# HUD.net
KiCad netlist of a schematic drawn in EAGLE
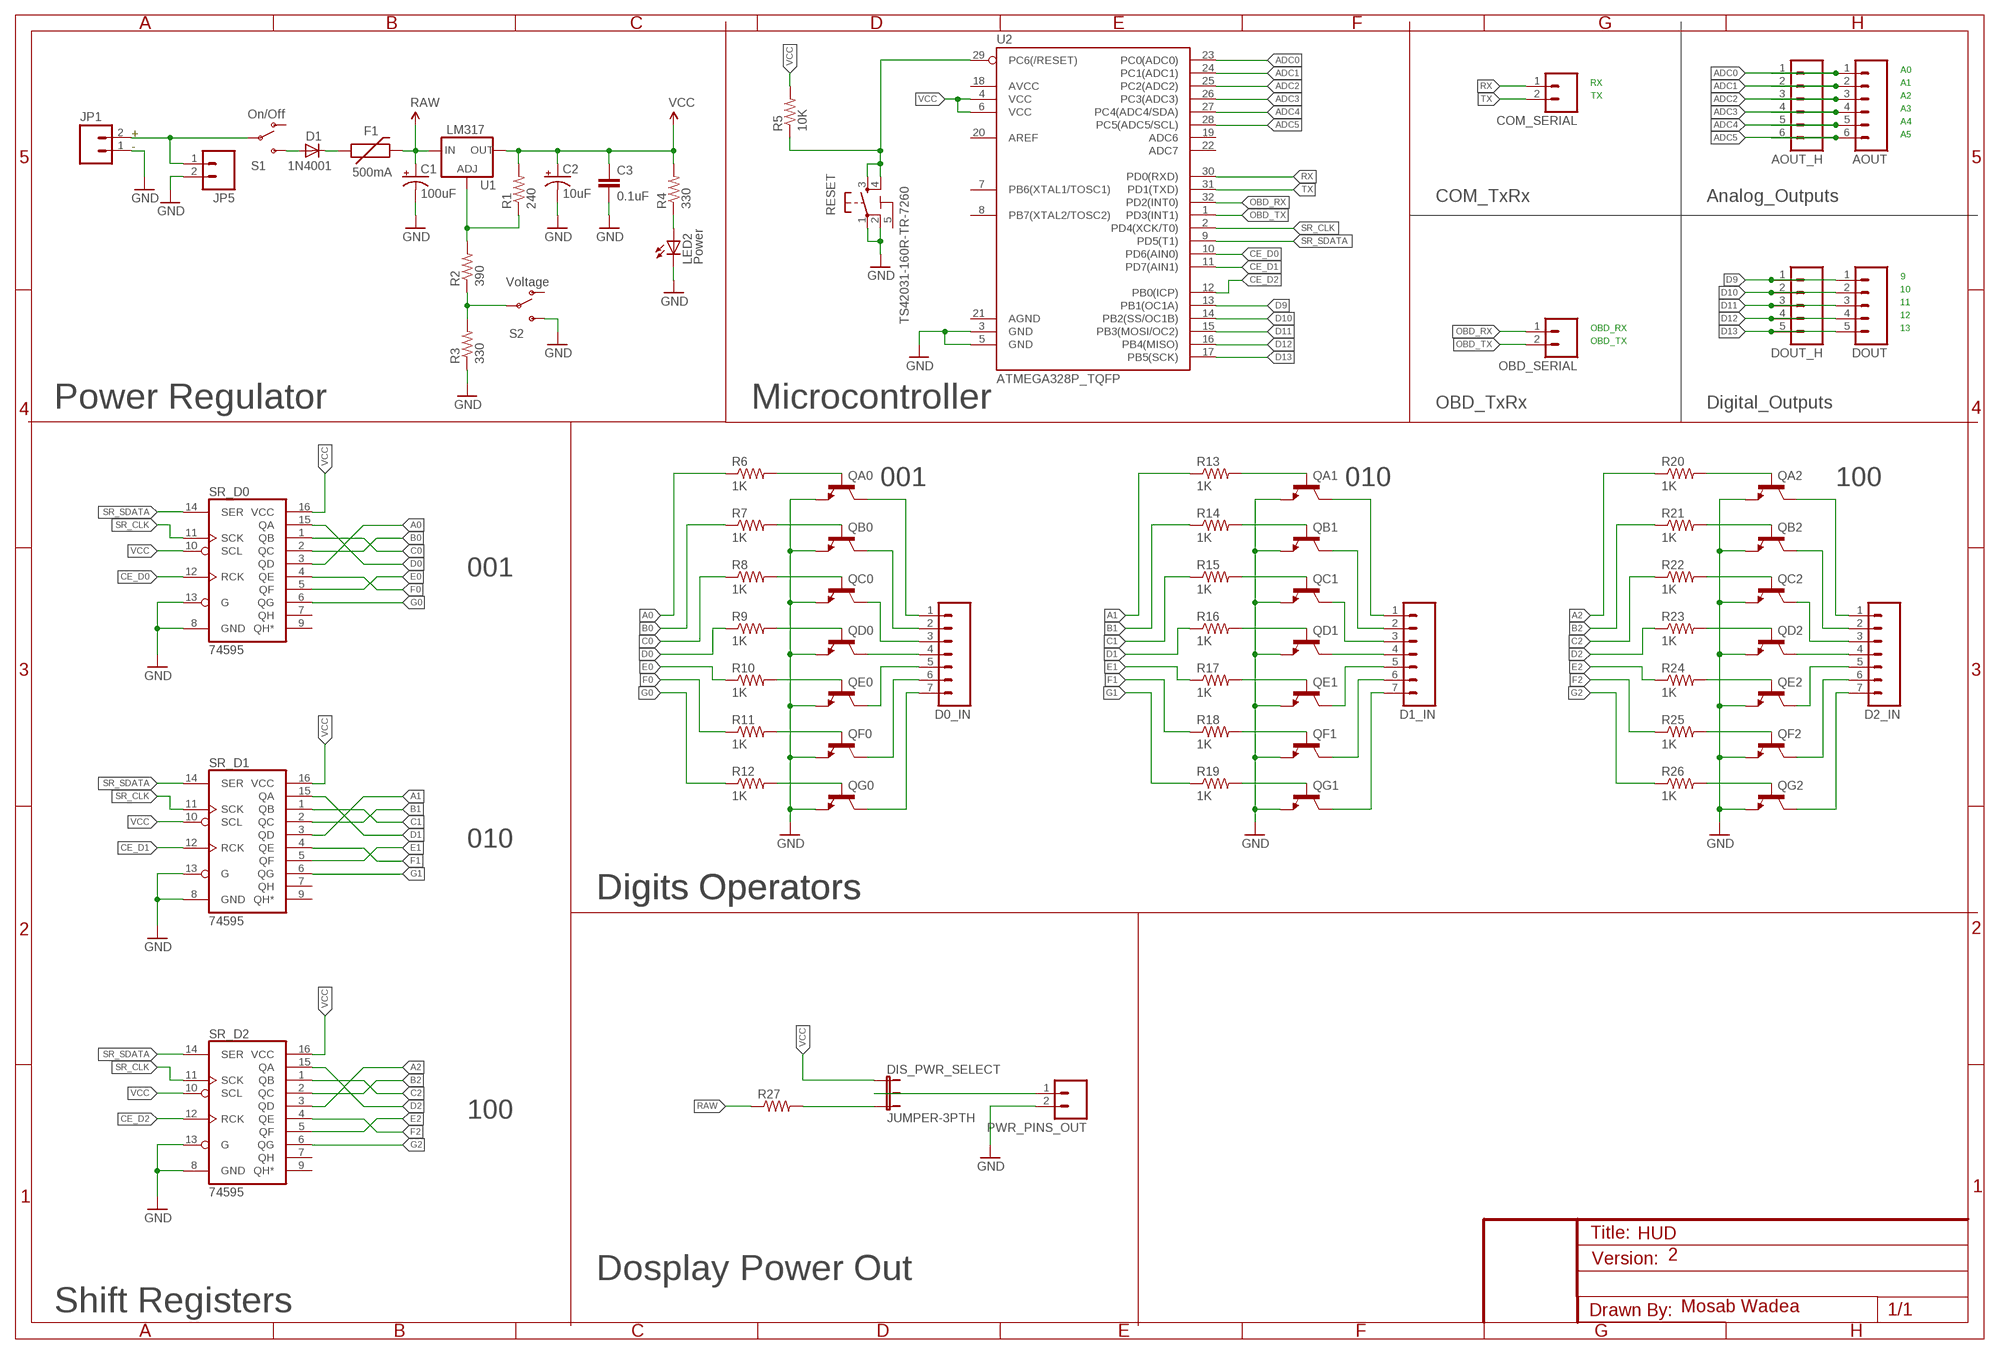
[diagram p0: schematic, sheet 1]

(export (version "E")
  (design (tool "Eeschema 10.0.6"))
  (components
    (comp (ref "AOUT")
      (value "M06SILK_FEMALE_PTH")
      (footprint "eagle-import:1X06")
      (libsource (lib "eagle-import") (part "M06SILK_FEMALE_PTH"))
    )
    (comp (ref "AOUT_H")
      (value "M06SILK_FEMALE_PTH")
      (footprint "eagle-import:1X06")
      (libsource (lib "eagle-import") (part "M06SILK_FEMALE_PTH"))
    )
    (comp (ref "C1")
      (value "100uF")
      (footprint "eagle-import:CPOL-RADIAL-100UF-25V")
      (libsource (lib "eagle-import") (part "CAP_POLPTH1"))
    )
    (comp (ref "C2")
      (value "10uF")
      (footprint "eagle-import:CPOL-RADIAL-10UF-25V")
      (libsource (lib "eagle-import") (part "CAP_POLPTH2"))
    )
    (comp (ref "C3")
      (value "0.1uF")
      (footprint "eagle-import:CAP-PTH-SMALL2")
      (libsource (lib "eagle-import") (part "CAPPTH2"))
    )
    (comp (ref "COM_SERIAL")
      (value "M02PTH")
      (footprint "eagle-import:1X02")
      (libsource (lib "eagle-import") (part "SparkFun-Connectors_M02PTH"))
    )
    (comp (ref "D0_IN")
      (value "M07")
      (footprint "eagle-import:1X07")
      (libsource (lib "eagle-import") (part "M07"))
    )
    (comp (ref "D1")
      (value "1N4001")
      (footprint "eagle-import:DIODE-0.4")
      (libsource (lib "eagle-import") (part "DIODEPTH"))
    )
    (comp (ref "D1_IN")
      (value "M07")
      (footprint "eagle-import:1X07")
      (libsource (lib "eagle-import") (part "M07"))
    )
    (comp (ref "D2_IN")
      (value "M07")
      (footprint "eagle-import:1X07")
      (libsource (lib "eagle-import") (part "M07"))
    )
    (comp (ref "DIS_PWR_SELECT")
      (value "JUMPER-3PTH")
      (footprint "eagle-import:1X03")
      (libsource (lib "eagle-import") (part "JUMPER-3PTH"))
    )
    (comp (ref "DOUT")
      (value "M05PTH")
      (footprint "eagle-import:1X05")
      (libsource (lib "eagle-import") (part "M05PTH"))
    )
    (comp (ref "DOUT_H")
      (value "M05PTH")
      (footprint "eagle-import:1X05")
      (libsource (lib "eagle-import") (part "M05PTH"))
    )
    (comp (ref "F1")
      (value "500mA")
      (footprint "eagle-import:PTC")
      (libsource (lib "eagle-import") (part "PTCPTH"))
    )
    (comp (ref "JP1")
      (value "M02PTH")
      (footprint "eagle-import:1X02")
      (libsource (lib "eagle-import") (part "SparkFun-Connectors_M02PTH"))
    )
    (comp (ref "JP5")
      (value "M02PTH")
      (footprint "eagle-import:1X02")
      (libsource (lib "eagle-import") (part "M02PTH"))
    )
    (comp (ref "LED2")
      (value "Power")
      (footprint "eagle-import:LED5MM")
      (libsource (lib "eagle-import") (part "LED5MM"))
    )
    (comp (ref "OBD_SERIAL")
      (value "M02PTH")
      (footprint "eagle-import:1X02")
      (libsource (lib "eagle-import") (part "SparkFun-Connectors_M02PTH"))
    )
    (comp (ref "PWR_PINS_OUT")
      (value "M02PTH")
      (footprint "eagle-import:1X02")
      (libsource (lib "eagle-import") (part "SparkFun-Connectors_M02PTH"))
    )
    (comp (ref "QA0")
      (value "TRANSISTOR_NPNP2N2222A")
      (footprint "eagle-import:TO-92")
      (libsource (lib "eagle-import") (part "TRANSISTOR_NPNP2N2222A"))
    )
    (comp (ref "QA1")
      (value "TRANSISTOR_NPNP2N2222A")
      (footprint "eagle-import:TO-92")
      (libsource (lib "eagle-import") (part "TRANSISTOR_NPNP2N2222A"))
    )
    (comp (ref "QA2")
      (value "TRANSISTOR_NPNP2N2222A")
      (footprint "eagle-import:TO-92")
      (libsource (lib "eagle-import") (part "TRANSISTOR_NPNP2N2222A"))
    )
    (comp (ref "QB0")
      (value "TRANSISTOR_NPNP2N2222A")
      (footprint "eagle-import:TO-92")
      (libsource (lib "eagle-import") (part "TRANSISTOR_NPNP2N2222A"))
    )
    (comp (ref "QB1")
      (value "TRANSISTOR_NPNP2N2222A")
      (footprint "eagle-import:TO-92")
      (libsource (lib "eagle-import") (part "TRANSISTOR_NPNP2N2222A"))
    )
    (comp (ref "QB2")
      (value "TRANSISTOR_NPNP2N2222A")
      (footprint "eagle-import:TO-92")
      (libsource (lib "eagle-import") (part "TRANSISTOR_NPNP2N2222A"))
    )
    (comp (ref "QC0")
      (value "TRANSISTOR_NPNP2N2222A")
      (footprint "eagle-import:TO-92")
      (libsource (lib "eagle-import") (part "TRANSISTOR_NPNP2N2222A"))
    )
    (comp (ref "QC1")
      (value "TRANSISTOR_NPNP2N2222A")
      (footprint "eagle-import:TO-92")
      (libsource (lib "eagle-import") (part "TRANSISTOR_NPNP2N2222A"))
    )
    (comp (ref "QC2")
      (value "TRANSISTOR_NPNP2N2222A")
      (footprint "eagle-import:TO-92")
      (libsource (lib "eagle-import") (part "TRANSISTOR_NPNP2N2222A"))
    )
    (comp (ref "QD0")
      (value "TRANSISTOR_NPNP2N2222A")
      (footprint "eagle-import:TO-92")
      (libsource (lib "eagle-import") (part "TRANSISTOR_NPNP2N2222A"))
    )
    (comp (ref "QD1")
      (value "TRANSISTOR_NPNP2N2222A")
      (footprint "eagle-import:TO-92")
      (libsource (lib "eagle-import") (part "TRANSISTOR_NPNP2N2222A"))
    )
    (comp (ref "QD2")
      (value "TRANSISTOR_NPNP2N2222A")
      (footprint "eagle-import:TO-92")
      (libsource (lib "eagle-import") (part "TRANSISTOR_NPNP2N2222A"))
    )
    (comp (ref "QE0")
      (value "TRANSISTOR_NPNP2N2222A")
      (footprint "eagle-import:TO-92")
      (libsource (lib "eagle-import") (part "TRANSISTOR_NPNP2N2222A"))
    )
    (comp (ref "QE1")
      (value "TRANSISTOR_NPNP2N2222A")
      (footprint "eagle-import:TO-92")
      (libsource (lib "eagle-import") (part "TRANSISTOR_NPNP2N2222A"))
    )
    (comp (ref "QE2")
      (value "TRANSISTOR_NPNP2N2222A")
      (footprint "eagle-import:TO-92")
      (libsource (lib "eagle-import") (part "TRANSISTOR_NPNP2N2222A"))
    )
    (comp (ref "QF0")
      (value "TRANSISTOR_NPNP2N2222A")
      (footprint "eagle-import:TO-92")
      (libsource (lib "eagle-import") (part "TRANSISTOR_NPNP2N2222A"))
    )
    (comp (ref "QF1")
      (value "TRANSISTOR_NPNP2N2222A")
      (footprint "eagle-import:TO-92")
      (libsource (lib "eagle-import") (part "TRANSISTOR_NPNP2N2222A"))
    )
    (comp (ref "QF2")
      (value "TRANSISTOR_NPNP2N2222A")
      (footprint "eagle-import:TO-92")
      (libsource (lib "eagle-import") (part "TRANSISTOR_NPNP2N2222A"))
    )
    (comp (ref "QG0")
      (value "TRANSISTOR_NPNP2N2222A")
      (footprint "eagle-import:TO-92")
      (libsource (lib "eagle-import") (part "TRANSISTOR_NPNP2N2222A"))
    )
    (comp (ref "QG1")
      (value "TRANSISTOR_NPNP2N2222A")
      (footprint "eagle-import:TO-92")
      (libsource (lib "eagle-import") (part "TRANSISTOR_NPNP2N2222A"))
    )
    (comp (ref "QG2")
      (value "TRANSISTOR_NPNP2N2222A")
      (footprint "eagle-import:TO-92")
      (libsource (lib "eagle-import") (part "TRANSISTOR_NPNP2N2222A"))
    )
    (comp (ref "R1")
      (value "240")
      (footprint "eagle-import:AXIAL-0.3")
      (libsource (lib "eagle-import") (part "RESISTORPTH1"))
    )
    (comp (ref "R2")
      (value "390")
      (footprint "eagle-import:AXIAL-0.3")
      (libsource (lib "eagle-import") (part "RESISTORPTH1"))
    )
    (comp (ref "R3")
      (value "330")
      (footprint "eagle-import:AXIAL-0.3")
      (libsource (lib "eagle-import") (part "RESISTORPTH1"))
    )
    (comp (ref "R4")
      (value "330")
      (footprint "eagle-import:AXIAL-0.3")
      (libsource (lib "eagle-import") (part "RESISTORPTH1"))
    )
    (comp (ref "R5")
      (value "10K")
      (footprint "eagle-import:AXIAL-0.4")
      (libsource (lib "eagle-import") (part "RESISTORPTH-1/4W"))
    )
    (comp (ref "R6")
      (value "1K")
      (footprint "eagle-import:AXIAL-0.4")
      (libsource (lib "eagle-import") (part "RESISTORPTH-1/4W"))
    )
    (comp (ref "R7")
      (value "1K")
      (footprint "eagle-import:AXIAL-0.4")
      (libsource (lib "eagle-import") (part "RESISTORPTH-1/4W"))
    )
    (comp (ref "R8")
      (value "1K")
      (footprint "eagle-import:AXIAL-0.4")
      (libsource (lib "eagle-import") (part "RESISTORPTH-1/4W"))
    )
    (comp (ref "R9")
      (value "1K")
      (footprint "eagle-import:AXIAL-0.4")
      (libsource (lib "eagle-import") (part "RESISTORPTH-1/4W"))
    )
    (comp (ref "R10")
      (value "1K")
      (footprint "eagle-import:AXIAL-0.4")
      (libsource (lib "eagle-import") (part "RESISTORPTH-1/4W"))
    )
    (comp (ref "R11")
      (value "1K")
      (footprint "eagle-import:AXIAL-0.4")
      (libsource (lib "eagle-import") (part "RESISTORPTH-1/4W"))
    )
    (comp (ref "R12")
      (value "1K")
      (footprint "eagle-import:AXIAL-0.4")
      (libsource (lib "eagle-import") (part "RESISTORPTH-1/4W"))
    )
    (comp (ref "R13")
      (value "1K")
      (footprint "eagle-import:AXIAL-0.4")
      (libsource (lib "eagle-import") (part "RESISTORPTH-1/4W"))
    )
    (comp (ref "R14")
      (value "1K")
      (footprint "eagle-import:AXIAL-0.4")
      (libsource (lib "eagle-import") (part "RESISTORPTH-1/4W"))
    )
    (comp (ref "R15")
      (value "1K")
      (footprint "eagle-import:AXIAL-0.4")
      (libsource (lib "eagle-import") (part "RESISTORPTH-1/4W"))
    )
    (comp (ref "R16")
      (value "1K")
      (footprint "eagle-import:AXIAL-0.4")
      (libsource (lib "eagle-import") (part "RESISTORPTH-1/4W"))
    )
    (comp (ref "R17")
      (value "1K")
      (footprint "eagle-import:AXIAL-0.4")
      (libsource (lib "eagle-import") (part "RESISTORPTH-1/4W"))
    )
    (comp (ref "R18")
      (value "1K")
      (footprint "eagle-import:AXIAL-0.4")
      (libsource (lib "eagle-import") (part "RESISTORPTH-1/4W"))
    )
    (comp (ref "R19")
      (value "1K")
      (footprint "eagle-import:AXIAL-0.4")
      (libsource (lib "eagle-import") (part "RESISTORPTH-1/4W"))
    )
    (comp (ref "R20")
      (value "1K")
      (footprint "eagle-import:AXIAL-0.4")
      (libsource (lib "eagle-import") (part "RESISTORPTH-1/4W"))
    )
    (comp (ref "R21")
      (value "1K")
      (footprint "eagle-import:AXIAL-0.4")
      (libsource (lib "eagle-import") (part "RESISTORPTH-1/4W"))
    )
    (comp (ref "R22")
      (value "1K")
      (footprint "eagle-import:AXIAL-0.4")
      (libsource (lib "eagle-import") (part "RESISTORPTH-1/4W"))
    )
    (comp (ref "R23")
      (value "1K")
      (footprint "eagle-import:AXIAL-0.4")
      (libsource (lib "eagle-import") (part "RESISTORPTH-1/4W"))
    )
    (comp (ref "R24")
      (value "1K")
      (footprint "eagle-import:AXIAL-0.4")
      (libsource (lib "eagle-import") (part "RESISTORPTH-1/4W"))
    )
    (comp (ref "R25")
      (value "1K")
      (footprint "eagle-import:AXIAL-0.4")
      (libsource (lib "eagle-import") (part "RESISTORPTH-1/4W"))
    )
    (comp (ref "R26")
      (value "1K")
      (footprint "eagle-import:AXIAL-0.4")
      (libsource (lib "eagle-import") (part "RESISTORPTH-1/4W"))
    )
    (comp (ref "R27")
      (value "RESISTORPTH-1/4W")
      (footprint "eagle-import:AXIAL-0.4")
      (libsource (lib "eagle-import") (part "RESISTORPTH-1/4W"))
    )
    (comp (ref "RESET")
      (value "TS42031-160R-TR-7260")
      (footprint "eagle-import:TS42")
      (libsource (lib "eagle-import") (part "TS42"))
    )
    (comp (ref "S1")
      (value "On/Off")
      (footprint "eagle-import:SWITCH-SPST")
      (libsource (lib "eagle-import") (part "SWITCH-SPSTPTH"))
    )
    (comp (ref "S2")
      (value "Voltage")
      (footprint "eagle-import:SWITCH-SPST")
      (libsource (lib "eagle-import") (part "SWITCH-SPSTPTH"))
    )
    (comp (ref "SR_D0")
      (value "74595")
      (footprint "eagle-import:TSSOP16")
      (libsource (lib "eagle-import") (part "74595"))
    )
    (comp (ref "SR_D1")
      (value "74595")
      (footprint "eagle-import:TSSOP16")
      (libsource (lib "eagle-import") (part "74595"))
    )
    (comp (ref "SR_D2")
      (value "74595")
      (footprint "eagle-import:TSSOP16")
      (libsource (lib "eagle-import") (part "74595"))
    )
    (comp (ref "U1")
      (value "LM317")
      (footprint "eagle-import:TO220-ADJ")
      (libsource (lib "eagle-import") (part "V_REG_317SINK"))
    )
    (comp (ref "U2")
      (value "ATMEGA328P_TQFP")
      (footprint "eagle-import:TQFP32-08")
      (libsource (lib "eagle-import") (part "ATMEGA328P_TQFP"))
    )
  )
  (nets
    (net (code "1") (name "/5-GND") (class "Default")
      (node (ref "RESET") (pin "5") (pinfunction "5-GND_5") (pintype "power_in"))
    )
    (net (code "2") (name "A0") (class "Default")
      (node (ref "R6") (pin "P$1") (pinfunction "1_P$1") (pintype "passive"))
      (node (ref "SR_D0") (pin "3") (pinfunction "QD_3") (pintype "tri_state"))
    )
    (net (code "3") (name "A1") (class "Default")
      (node (ref "R13") (pin "P$1") (pinfunction "1_P$1") (pintype "passive"))
      (node (ref "SR_D1") (pin "3") (pinfunction "QD_3") (pintype "tri_state"))
    )
    (net (code "4") (name "A2") (class "Default")
      (node (ref "R20") (pin "P$1") (pinfunction "1_P$1") (pintype "passive"))
      (node (ref "SR_D2") (pin "3") (pinfunction "QD_3") (pintype "tri_state"))
    )
    (net (code "5") (name "ADC0") (class "Default")
      (node (ref "AOUT") (pin "1") (pinfunction "1_1") (pintype "passive"))
      (node (ref "AOUT_H") (pin "1") (pinfunction "1_1") (pintype "passive"))
      (node (ref "U2") (pin "23") (pinfunction "PC0(ADC0)_23") (pintype "bidirectional"))
    )
    (net (code "6") (name "ADC1") (class "Default")
      (node (ref "AOUT") (pin "2") (pinfunction "2_2") (pintype "passive"))
      (node (ref "AOUT_H") (pin "2") (pinfunction "2_2") (pintype "passive"))
      (node (ref "U2") (pin "24") (pinfunction "PC1(ADC1)_24") (pintype "bidirectional"))
    )
    (net (code "7") (name "ADC2") (class "Default")
      (node (ref "AOUT") (pin "3") (pinfunction "3_3") (pintype "passive"))
      (node (ref "AOUT_H") (pin "3") (pinfunction "3_3") (pintype "passive"))
      (node (ref "U2") (pin "25") (pinfunction "PC2(ADC2)_25") (pintype "bidirectional"))
    )
    (net (code "8") (name "ADC3") (class "Default")
      (node (ref "AOUT") (pin "4") (pinfunction "4_4") (pintype "passive"))
      (node (ref "AOUT_H") (pin "4") (pinfunction "4_4") (pintype "passive"))
      (node (ref "U2") (pin "26") (pinfunction "PC3(ADC3)_26") (pintype "bidirectional"))
    )
    (net (code "9") (name "ADC4") (class "Default")
      (node (ref "AOUT") (pin "5") (pinfunction "5_5") (pintype "passive"))
      (node (ref "AOUT_H") (pin "5") (pinfunction "5_5") (pintype "passive"))
      (node (ref "U2") (pin "27") (pinfunction "PC4(ADC4/SDA)_27") (pintype "bidirectional"))
    )
    (net (code "10") (name "ADC5") (class "Default")
      (node (ref "AOUT") (pin "6") (pinfunction "6_6") (pintype "passive"))
      (node (ref "AOUT_H") (pin "6") (pinfunction "6_6") (pintype "passive"))
      (node (ref "U2") (pin "28") (pinfunction "PC5(ADC5/SCL)_28") (pintype "bidirectional"))
    )
    (net (code "11") (name "B0") (class "Default")
      (node (ref "R7") (pin "P$1") (pinfunction "1_P$1") (pintype "passive"))
      (node (ref "SR_D0") (pin "2") (pinfunction "QC_2") (pintype "tri_state"))
    )
    (net (code "12") (name "B1") (class "Default")
      (node (ref "R14") (pin "P$1") (pinfunction "1_P$1") (pintype "passive"))
      (node (ref "SR_D1") (pin "2") (pinfunction "QC_2") (pintype "tri_state"))
    )
    (net (code "13") (name "B2") (class "Default")
      (node (ref "R21") (pin "P$1") (pinfunction "1_P$1") (pintype "passive"))
      (node (ref "SR_D2") (pin "2") (pinfunction "QC_2") (pintype "tri_state"))
    )
    (net (code "14") (name "C0") (class "Default")
      (node (ref "R8") (pin "P$1") (pinfunction "1_P$1") (pintype "passive"))
      (node (ref "SR_D0") (pin "1") (pinfunction "QB_1") (pintype "tri_state"))
    )
    (net (code "15") (name "C1") (class "Default")
      (node (ref "R15") (pin "P$1") (pinfunction "1_P$1") (pintype "passive"))
      (node (ref "SR_D1") (pin "1") (pinfunction "QB_1") (pintype "tri_state"))
    )
    (net (code "16") (name "C2") (class "Default")
      (node (ref "R22") (pin "P$1") (pinfunction "1_P$1") (pintype "passive"))
      (node (ref "SR_D2") (pin "1") (pinfunction "QB_1") (pintype "tri_state"))
    )
    (net (code "17") (name "CE_D0") (class "Default")
      (node (ref "SR_D0") (pin "12") (pinfunction "RCK_12") (pintype "input"))
      (node (ref "U2") (pin "10") (pinfunction "PD6(AIN0)_10") (pintype "bidirectional"))
    )
    (net (code "18") (name "CE_D1") (class "Default")
      (node (ref "SR_D1") (pin "12") (pinfunction "RCK_12") (pintype "input"))
      (node (ref "U2") (pin "11") (pinfunction "PD7(AIN1)_11") (pintype "bidirectional"))
    )
    (net (code "19") (name "CE_D2") (class "Default")
      (node (ref "SR_D2") (pin "12") (pinfunction "RCK_12") (pintype "input"))
      (node (ref "U2") (pin "12") (pinfunction "PB0(ICP)_12") (pintype "bidirectional"))
    )
    (net (code "20") (name "D0") (class "Default")
      (node (ref "R9") (pin "P$1") (pinfunction "1_P$1") (pintype "passive"))
      (node (ref "SR_D0") (pin "15") (pinfunction "QA_15") (pintype "tri_state"))
    )
    (net (code "21") (name "D1") (class "Default")
      (node (ref "R16") (pin "P$1") (pinfunction "1_P$1") (pintype "passive"))
      (node (ref "SR_D1") (pin "15") (pinfunction "QA_15") (pintype "tri_state"))
    )
    (net (code "22") (name "D2") (class "Default")
      (node (ref "R23") (pin "P$1") (pinfunction "1_P$1") (pintype "passive"))
      (node (ref "SR_D2") (pin "15") (pinfunction "QA_15") (pintype "tri_state"))
    )
    (net (code "23") (name "D9") (class "Default")
      (node (ref "DOUT") (pin "1") (pinfunction "1_1") (pintype "passive"))
      (node (ref "DOUT_H") (pin "1") (pinfunction "1_1") (pintype "passive"))
      (node (ref "U2") (pin "13") (pinfunction "PB1(OC1A)_13") (pintype "bidirectional"))
    )
    (net (code "24") (name "D10") (class "Default")
      (node (ref "DOUT") (pin "2") (pinfunction "2_2") (pintype "passive"))
      (node (ref "DOUT_H") (pin "2") (pinfunction "2_2") (pintype "passive"))
      (node (ref "U2") (pin "14") (pinfunction "PB2(SS/OC1B)_14") (pintype "bidirectional"))
    )
    (net (code "25") (name "D11") (class "Default")
      (node (ref "DOUT") (pin "3") (pinfunction "3_3") (pintype "passive"))
      (node (ref "DOUT_H") (pin "3") (pinfunction "3_3") (pintype "passive"))
      (node (ref "U2") (pin "15") (pinfunction "PB3(MOSI/OC2)_15") (pintype "bidirectional"))
    )
    (net (code "26") (name "D12") (class "Default")
      (node (ref "DOUT") (pin "4") (pinfunction "4_4") (pintype "passive"))
      (node (ref "DOUT_H") (pin "4") (pinfunction "4_4") (pintype "passive"))
      (node (ref "U2") (pin "16") (pinfunction "PB4(MISO)_16") (pintype "bidirectional"))
    )
    (net (code "27") (name "D13") (class "Default")
      (node (ref "DOUT") (pin "5") (pinfunction "5_5") (pintype "passive"))
      (node (ref "DOUT_H") (pin "5") (pinfunction "5_5") (pintype "passive"))
      (node (ref "U2") (pin "17") (pinfunction "PB5(SCK)_17") (pintype "bidirectional"))
    )
    (net (code "28") (name "E0") (class "Default")
      (node (ref "R10") (pin "P$1") (pinfunction "1_P$1") (pintype "passive"))
      (node (ref "SR_D0") (pin "5") (pinfunction "QF_5") (pintype "tri_state"))
    )
    (net (code "29") (name "E1") (class "Default")
      (node (ref "R17") (pin "P$1") (pinfunction "1_P$1") (pintype "passive"))
      (node (ref "SR_D1") (pin "5") (pinfunction "QF_5") (pintype "tri_state"))
    )
    (net (code "30") (name "E2") (class "Default")
      (node (ref "R24") (pin "P$1") (pinfunction "1_P$1") (pintype "passive"))
      (node (ref "SR_D2") (pin "5") (pinfunction "QF_5") (pintype "tri_state"))
    )
    (net (code "31") (name "F0") (class "Default")
      (node (ref "R11") (pin "P$1") (pinfunction "1_P$1") (pintype "passive"))
      (node (ref "SR_D0") (pin "4") (pinfunction "QE_4") (pintype "tri_state"))
    )
    (net (code "32") (name "F1") (class "Default")
      (node (ref "R18") (pin "P$1") (pinfunction "1_P$1") (pintype "passive"))
      (node (ref "SR_D1") (pin "4") (pinfunction "QE_4") (pintype "tri_state"))
    )
    (net (code "33") (name "F2") (class "Default")
      (node (ref "R25") (pin "P$1") (pinfunction "1_P$1") (pintype "passive"))
      (node (ref "SR_D2") (pin "4") (pinfunction "QE_4") (pintype "tri_state"))
    )
    (net (code "34") (name "G0") (class "Default")
      (node (ref "R12") (pin "P$1") (pinfunction "1_P$1") (pintype "passive"))
      (node (ref "SR_D0") (pin "6") (pinfunction "QG_6") (pintype "tri_state"))
    )
    (net (code "35") (name "G1") (class "Default")
      (node (ref "R19") (pin "P$1") (pinfunction "1_P$1") (pintype "passive"))
      (node (ref "SR_D1") (pin "6") (pinfunction "QG_6") (pintype "tri_state"))
    )
    (net (code "36") (name "G2") (class "Default")
      (node (ref "R26") (pin "P$1") (pinfunction "1_P$1") (pintype "passive"))
      (node (ref "SR_D2") (pin "6") (pinfunction "QG_6") (pintype "tri_state"))
    )
    (net (code "37") (name "GND") (class "Default")
      (node (ref "C1") (pin "2") (pinfunction "-_2") (pintype "passive"))
      (node (ref "C2") (pin "2") (pinfunction "-_2") (pintype "passive"))
      (node (ref "C3") (pin "2") (pinfunction "2_2") (pintype "passive"))
      (node (ref "JP1") (pin "1") (pinfunction "1_1") (pintype "passive"))
      (node (ref "JP5") (pin "2") (pinfunction "2_2") (pintype "passive"))
      (node (ref "LED2") (pin "K") (pinfunction "C_K") (pintype "passive"))
      (node (ref "PWR_PINS_OUT") (pin "2") (pinfunction "2_2") (pintype "passive"))
      (node (ref "QA0") (pin "3") (pinfunction "E_3") (pintype "passive"))
      (node (ref "QA1") (pin "3") (pinfunction "E_3") (pintype "passive"))
      (node (ref "QA2") (pin "3") (pinfunction "E_3") (pintype "passive"))
      (node (ref "QB0") (pin "3") (pinfunction "E_3") (pintype "passive"))
      (node (ref "QB1") (pin "3") (pinfunction "E_3") (pintype "passive"))
      (node (ref "QB2") (pin "3") (pinfunction "E_3") (pintype "passive"))
      (node (ref "QC0") (pin "3") (pinfunction "E_3") (pintype "passive"))
      (node (ref "QC1") (pin "3") (pinfunction "E_3") (pintype "passive"))
      (node (ref "QC2") (pin "3") (pinfunction "E_3") (pintype "passive"))
      (node (ref "QD0") (pin "3") (pinfunction "E_3") (pintype "passive"))
      (node (ref "QD1") (pin "3") (pinfunction "E_3") (pintype "passive"))
      (node (ref "QD2") (pin "3") (pinfunction "E_3") (pintype "passive"))
      (node (ref "QE0") (pin "3") (pinfunction "E_3") (pintype "passive"))
      (node (ref "QE1") (pin "3") (pinfunction "E_3") (pintype "passive"))
      (node (ref "QE2") (pin "3") (pinfunction "E_3") (pintype "passive"))
      (node (ref "QF0") (pin "3") (pinfunction "E_3") (pintype "passive"))
      (node (ref "QF1") (pin "3") (pinfunction "E_3") (pintype "passive"))
      (node (ref "QF2") (pin "3") (pinfunction "E_3") (pintype "passive"))
      (node (ref "QG0") (pin "3") (pinfunction "E_3") (pintype "passive"))
      (node (ref "QG1") (pin "3") (pinfunction "E_3") (pintype "passive"))
      (node (ref "QG2") (pin "3") (pinfunction "E_3") (pintype "passive"))
      (node (ref "R3") (pin "P$1") (pinfunction "1_P$1") (pintype "passive"))
      (node (ref "RESET") (pin "1") (pinfunction "1_1") (pintype "passive"))
      (node (ref "RESET") (pin "2") (pinfunction "2_2") (pintype "passive"))
      (node (ref "S2") (pin "3") (pinfunction "S_3") (pintype "passive"))
      (node (ref "SR_D0") (pin "13") (pinfunction "G_13") (pintype "input"))
      (node (ref "SR_D0") (pin "8") (pinfunction "GND_8") (pintype "power_in"))
      (node (ref "SR_D1") (pin "13") (pinfunction "G_13") (pintype "input"))
      (node (ref "SR_D1") (pin "8") (pinfunction "GND_8") (pintype "power_in"))
      (node (ref "SR_D2") (pin "13") (pinfunction "G_13") (pintype "input"))
      (node (ref "SR_D2") (pin "8") (pinfunction "GND_8") (pintype "power_in"))
      (node (ref "U2") (pin "3") (pinfunction "GND_3") (pintype "bidirectional"))
      (node (ref "U2") (pin "5") (pinfunction "GND_5") (pintype "bidirectional"))
    )
    (net (code "38") (name "Net-(DIS_PWR_SELECT-Pad2)") (class "Default")
      (node (ref "DIS_PWR_SELECT") (pin "2") (pinfunction "2_2") (pintype "passive"))
      (node (ref "PWR_PINS_OUT") (pin "1") (pinfunction "1_1") (pintype "passive"))
    )
    (net (code "39") (name "Net-(F1-1)") (class "Default")
      (node (ref "D1") (pin "C") (pinfunction "C_C") (pintype "passive"))
      (node (ref "F1") (pin "P$1") (pinfunction "1_P$1") (pintype "bidirectional"))
    )
    (net (code "40") (name "Net-(QA0-B)") (class "Default")
      (node (ref "QA0") (pin "2") (pinfunction "B_2") (pintype "passive"))
      (node (ref "R6") (pin "P$2") (pinfunction "2_P$2") (pintype "passive"))
    )
    (net (code "41") (name "Net-(QA0-C)") (class "Default")
      (node (ref "D0_IN") (pin "1") (pinfunction "1_1") (pintype "passive"))
      (node (ref "QA0") (pin "1") (pinfunction "C_1") (pintype "passive"))
    )
    (net (code "42") (name "Net-(QA1-B)") (class "Default")
      (node (ref "QA1") (pin "2") (pinfunction "B_2") (pintype "passive"))
      (node (ref "R13") (pin "P$2") (pinfunction "2_P$2") (pintype "passive"))
    )
    (net (code "43") (name "Net-(QA1-C)") (class "Default")
      (node (ref "D1_IN") (pin "1") (pinfunction "1_1") (pintype "passive"))
      (node (ref "QA1") (pin "1") (pinfunction "C_1") (pintype "passive"))
    )
    (net (code "44") (name "Net-(QA2-B)") (class "Default")
      (node (ref "QA2") (pin "2") (pinfunction "B_2") (pintype "passive"))
      (node (ref "R20") (pin "P$2") (pinfunction "2_P$2") (pintype "passive"))
    )
    (net (code "45") (name "Net-(QA2-C)") (class "Default")
      (node (ref "D2_IN") (pin "1") (pinfunction "1_1") (pintype "passive"))
      (node (ref "QA2") (pin "1") (pinfunction "C_1") (pintype "passive"))
    )
    (net (code "46") (name "Net-(QB0-B)") (class "Default")
      (node (ref "QB0") (pin "2") (pinfunction "B_2") (pintype "passive"))
      (node (ref "R7") (pin "P$2") (pinfunction "2_P$2") (pintype "passive"))
    )
    (net (code "47") (name "Net-(QB0-C)") (class "Default")
      (node (ref "D0_IN") (pin "2") (pinfunction "2_2") (pintype "passive"))
      (node (ref "QB0") (pin "1") (pinfunction "C_1") (pintype "passive"))
    )
    (net (code "48") (name "Net-(QB1-B)") (class "Default")
      (node (ref "QB1") (pin "2") (pinfunction "B_2") (pintype "passive"))
      (node (ref "R14") (pin "P$2") (pinfunction "2_P$2") (pintype "passive"))
    )
    (net (code "49") (name "Net-(QB1-C)") (class "Default")
      (node (ref "D1_IN") (pin "2") (pinfunction "2_2") (pintype "passive"))
      (node (ref "QB1") (pin "1") (pinfunction "C_1") (pintype "passive"))
    )
    (net (code "50") (name "Net-(QB2-B)") (class "Default")
      (node (ref "QB2") (pin "2") (pinfunction "B_2") (pintype "passive"))
      (node (ref "R21") (pin "P$2") (pinfunction "2_P$2") (pintype "passive"))
    )
    (net (code "51") (name "Net-(QB2-C)") (class "Default")
      (node (ref "D2_IN") (pin "2") (pinfunction "2_2") (pintype "passive"))
      (node (ref "QB2") (pin "1") (pinfunction "C_1") (pintype "passive"))
    )
    (net (code "52") (name "Net-(QC0-B)") (class "Default")
      (node (ref "QC0") (pin "2") (pinfunction "B_2") (pintype "passive"))
      (node (ref "R8") (pin "P$2") (pinfunction "2_P$2") (pintype "passive"))
    )
    (net (code "53") (name "Net-(QC0-C)") (class "Default")
      (node (ref "D0_IN") (pin "3") (pinfunction "3_3") (pintype "passive"))
      (node (ref "QC0") (pin "1") (pinfunction "C_1") (pintype "passive"))
    )
    (net (code "54") (name "Net-(QC1-B)") (class "Default")
      (node (ref "QC1") (pin "2") (pinfunction "B_2") (pintype "passive"))
      (node (ref "R15") (pin "P$2") (pinfunction "2_P$2") (pintype "passive"))
    )
    (net (code "55") (name "Net-(QC1-C)") (class "Default")
      (node (ref "D1_IN") (pin "3") (pinfunction "3_3") (pintype "passive"))
      (node (ref "QC1") (pin "1") (pinfunction "C_1") (pintype "passive"))
    )
    (net (code "56") (name "Net-(QC2-B)") (class "Default")
      (node (ref "QC2") (pin "2") (pinfunction "B_2") (pintype "passive"))
      (node (ref "R22") (pin "P$2") (pinfunction "2_P$2") (pintype "passive"))
    )
    (net (code "57") (name "Net-(QC2-C)") (class "Default")
      (node (ref "D2_IN") (pin "3") (pinfunction "3_3") (pintype "passive"))
      (node (ref "QC2") (pin "1") (pinfunction "C_1") (pintype "passive"))
    )
    (net (code "58") (name "Net-(QD0-B)") (class "Default")
      (node (ref "QD0") (pin "2") (pinfunction "B_2") (pintype "passive"))
      (node (ref "R9") (pin "P$2") (pinfunction "2_P$2") (pintype "passive"))
    )
    (net (code "59") (name "Net-(QD0-C)") (class "Default")
      (node (ref "D0_IN") (pin "4") (pinfunction "4_4") (pintype "passive"))
      (node (ref "QD0") (pin "1") (pinfunction "C_1") (pintype "passive"))
    )
    (net (code "60") (name "Net-(QD1-B)") (class "Default")
      (node (ref "QD1") (pin "2") (pinfunction "B_2") (pintype "passive"))
      (node (ref "R16") (pin "P$2") (pinfunction "2_P$2") (pintype "passive"))
    )
    (net (code "61") (name "Net-(QD1-C)") (class "Default")
      (node (ref "D1_IN") (pin "4") (pinfunction "4_4") (pintype "passive"))
      (node (ref "QD1") (pin "1") (pinfunction "C_1") (pintype "passive"))
    )
    (net (code "62") (name "Net-(QD2-B)") (class "Default")
      (node (ref "QD2") (pin "2") (pinfunction "B_2") (pintype "passive"))
      (node (ref "R23") (pin "P$2") (pinfunction "2_P$2") (pintype "passive"))
    )
    (net (code "63") (name "Net-(QD2-C)") (class "Default")
      (node (ref "D2_IN") (pin "4") (pinfunction "4_4") (pintype "passive"))
      (node (ref "QD2") (pin "1") (pinfunction "C_1") (pintype "passive"))
    )
    (net (code "64") (name "Net-(QE0-B)") (class "Default")
      (node (ref "QE0") (pin "2") (pinfunction "B_2") (pintype "passive"))
      (node (ref "R10") (pin "P$2") (pinfunction "2_P$2") (pintype "passive"))
    )
    (net (code "65") (name "Net-(QE0-C)") (class "Default")
      (node (ref "D0_IN") (pin "5") (pinfunction "5_5") (pintype "passive"))
      (node (ref "QE0") (pin "1") (pinfunction "C_1") (pintype "passive"))
    )
    (net (code "66") (name "Net-(QE1-B)") (class "Default")
      (node (ref "QE1") (pin "2") (pinfunction "B_2") (pintype "passive"))
      (node (ref "R17") (pin "P$2") (pinfunction "2_P$2") (pintype "passive"))
    )
    (net (code "67") (name "Net-(QE1-C)") (class "Default")
      (node (ref "D1_IN") (pin "5") (pinfunction "5_5") (pintype "passive"))
      (node (ref "QE1") (pin "1") (pinfunction "C_1") (pintype "passive"))
    )
    (net (code "68") (name "Net-(QE2-B)") (class "Default")
      (node (ref "QE2") (pin "2") (pinfunction "B_2") (pintype "passive"))
      (node (ref "R24") (pin "P$2") (pinfunction "2_P$2") (pintype "passive"))
    )
    (net (code "69") (name "Net-(QE2-C)") (class "Default")
      (node (ref "D2_IN") (pin "5") (pinfunction "5_5") (pintype "passive"))
      (node (ref "QE2") (pin "1") (pinfunction "C_1") (pintype "passive"))
    )
    (net (code "70") (name "Net-(QF0-B)") (class "Default")
      (node (ref "QF0") (pin "2") (pinfunction "B_2") (pintype "passive"))
      (node (ref "R11") (pin "P$2") (pinfunction "2_P$2") (pintype "passive"))
    )
    (net (code "71") (name "Net-(QF0-C)") (class "Default")
      (node (ref "D0_IN") (pin "6") (pinfunction "6_6") (pintype "passive"))
      (node (ref "QF0") (pin "1") (pinfunction "C_1") (pintype "passive"))
    )
    (net (code "72") (name "Net-(QF1-B)") (class "Default")
      (node (ref "QF1") (pin "2") (pinfunction "B_2") (pintype "passive"))
      (node (ref "R18") (pin "P$2") (pinfunction "2_P$2") (pintype "passive"))
    )
    (net (code "73") (name "Net-(QF1-C)") (class "Default")
      (node (ref "D1_IN") (pin "6") (pinfunction "6_6") (pintype "passive"))
      (node (ref "QF1") (pin "1") (pinfunction "C_1") (pintype "passive"))
    )
    (net (code "74") (name "Net-(QF2-B)") (class "Default")
      (node (ref "QF2") (pin "2") (pinfunction "B_2") (pintype "passive"))
      (node (ref "R25") (pin "P$2") (pinfunction "2_P$2") (pintype "passive"))
    )
    (net (code "75") (name "Net-(QF2-C)") (class "Default")
      (node (ref "D2_IN") (pin "6") (pinfunction "6_6") (pintype "passive"))
      (node (ref "QF2") (pin "1") (pinfunction "C_1") (pintype "passive"))
    )
    (net (code "76") (name "Net-(QG0-B)") (class "Default")
      (node (ref "QG0") (pin "2") (pinfunction "B_2") (pintype "passive"))
      (node (ref "R12") (pin "P$2") (pinfunction "2_P$2") (pintype "passive"))
    )
    (net (code "77") (name "Net-(QG0-C)") (class "Default")
      (node (ref "D0_IN") (pin "7") (pinfunction "7_7") (pintype "passive"))
      (node (ref "QG0") (pin "1") (pinfunction "C_1") (pintype "passive"))
    )
    (net (code "78") (name "Net-(QG1-B)") (class "Default")
      (node (ref "QG1") (pin "2") (pinfunction "B_2") (pintype "passive"))
      (node (ref "R19") (pin "P$2") (pinfunction "2_P$2") (pintype "passive"))
    )
    (net (code "79") (name "Net-(QG1-C)") (class "Default")
      (node (ref "D1_IN") (pin "7") (pinfunction "7_7") (pintype "passive"))
      (node (ref "QG1") (pin "1") (pinfunction "C_1") (pintype "passive"))
    )
    (net (code "80") (name "Net-(QG2-B)") (class "Default")
      (node (ref "QG2") (pin "2") (pinfunction "B_2") (pintype "passive"))
      (node (ref "R26") (pin "P$2") (pinfunction "2_P$2") (pintype "passive"))
    )
    (net (code "81") (name "Net-(QG2-C)") (class "Default")
      (node (ref "D2_IN") (pin "7") (pinfunction "7_7") (pintype "passive"))
      (node (ref "QG2") (pin "1") (pinfunction "C_1") (pintype "passive"))
    )
    (net (code "82") (name "Net-(R1-1)") (class "Default")
      (node (ref "R1") (pin "P$1") (pinfunction "1_P$1") (pintype "passive"))
      (node (ref "R2") (pin "P$2") (pinfunction "2_P$2") (pintype "passive"))
      (node (ref "U1") (pin "ADJ") (pinfunction "ADJ_ADJ") (pintype "input"))
    )
    (net (code "83") (name "Net-(R2-1)") (class "Default")
      (node (ref "R2") (pin "P$1") (pinfunction "1_P$1") (pintype "passive"))
      (node (ref "R3") (pin "P$2") (pinfunction "2_P$2") (pintype "passive"))
      (node (ref "S2") (pin "2") (pinfunction "P_2") (pintype "passive"))
    )
    (net (code "84") (name "Net-(R4-1)") (class "Default")
      (node (ref "LED2") (pin "A") (pinfunction "A_A") (pintype "passive"))
      (node (ref "R4") (pin "P$1") (pinfunction "1_P$1") (pintype "passive"))
    )
    (net (code "85") (name "Net-(R5-1)") (class "Default")
      (node (ref "R5") (pin "P$1") (pinfunction "1_P$1") (pintype "passive"))
      (node (ref "RESET") (pin "3") (pinfunction "3_3") (pintype "passive"))
      (node (ref "RESET") (pin "4") (pinfunction "4_4") (pintype "passive"))
      (node (ref "U2") (pin "29") (pinfunction "PC6(/RESET)_29") (pintype "bidirectional"))
    )
    (net (code "86") (name "Net-(R27-2)") (class "Default")
      (node (ref "DIS_PWR_SELECT") (pin "3") (pinfunction "3_3") (pintype "passive"))
      (node (ref "R27") (pin "P$2") (pinfunction "2_P$2") (pintype "passive"))
    )
    (net (code "87") (name "Net-(S1-P)") (class "Default")
      (node (ref "JP1") (pin "2") (pinfunction "2_2") (pintype "passive"))
      (node (ref "JP5") (pin "1") (pinfunction "1_1") (pintype "passive"))
      (node (ref "S1") (pin "2") (pinfunction "P_2") (pintype "passive"))
    )
    (net (code "88") (name "Net-(S1-S)") (class "Default")
      (node (ref "D1") (pin "A") (pinfunction "A_A") (pintype "passive"))
      (node (ref "S1") (pin "3") (pinfunction "S_3") (pintype "passive"))
    )
    (net (code "89") (name "OBD_RX") (class "Default")
      (node (ref "OBD_SERIAL") (pin "1") (pinfunction "1_1") (pintype "passive"))
      (node (ref "U2") (pin "32") (pinfunction "PD2(INT0)_32") (pintype "bidirectional"))
    )
    (net (code "90") (name "OBD_TX") (class "Default")
      (node (ref "OBD_SERIAL") (pin "2") (pinfunction "2_2") (pintype "passive"))
      (node (ref "U2") (pin "1") (pinfunction "PD3(INT1)_1") (pintype "bidirectional"))
    )
    (net (code "91") (name "RAW") (class "Default")
      (node (ref "C1") (pin "1") (pinfunction "+_1") (pintype "passive"))
      (node (ref "F1") (pin "P$2") (pinfunction "2_P$2") (pintype "bidirectional"))
      (node (ref "R27") (pin "P$1") (pinfunction "1_P$1") (pintype "passive"))
      (node (ref "U1") (pin "IN") (pinfunction "IN_IN") (pintype "input"))
    )
    (net (code "92") (name "RX") (class "Default")
      (node (ref "COM_SERIAL") (pin "1") (pinfunction "1_1") (pintype "passive"))
      (node (ref "U2") (pin "30") (pinfunction "PD0(RXD)_30") (pintype "bidirectional"))
    )
    (net (code "93") (name "SR_CLK") (class "Default")
      (node (ref "SR_D0") (pin "11") (pinfunction "SCK_11") (pintype "input"))
      (node (ref "SR_D1") (pin "11") (pinfunction "SCK_11") (pintype "input"))
      (node (ref "SR_D2") (pin "11") (pinfunction "SCK_11") (pintype "input"))
      (node (ref "U2") (pin "2") (pinfunction "PD4(XCK/T0)_2") (pintype "bidirectional"))
    )
    (net (code "94") (name "SR_SDATA") (class "Default")
      (node (ref "SR_D0") (pin "14") (pinfunction "SER_14") (pintype "input"))
      (node (ref "SR_D1") (pin "14") (pinfunction "SER_14") (pintype "input"))
      (node (ref "SR_D2") (pin "14") (pinfunction "SER_14") (pintype "input"))
      (node (ref "U2") (pin "9") (pinfunction "PD5(T1)_9") (pintype "bidirectional"))
    )
    (net (code "95") (name "TX") (class "Default")
      (node (ref "COM_SERIAL") (pin "2") (pinfunction "2_2") (pintype "passive"))
      (node (ref "U2") (pin "31") (pinfunction "PD1(TXD)_31") (pintype "bidirectional"))
    )
    (net (code "96") (name "VCC") (class "Default")
      (node (ref "C2") (pin "1") (pinfunction "+_1") (pintype "passive"))
      (node (ref "C3") (pin "1") (pinfunction "1_1") (pintype "passive"))
      (node (ref "DIS_PWR_SELECT") (pin "1") (pinfunction "1_1") (pintype "passive"))
      (node (ref "R1") (pin "P$2") (pinfunction "2_P$2") (pintype "passive"))
      (node (ref "R4") (pin "P$2") (pinfunction "2_P$2") (pintype "passive"))
      (node (ref "R5") (pin "P$2") (pinfunction "2_P$2") (pintype "passive"))
      (node (ref "SR_D0") (pin "10") (pinfunction "SCL_10") (pintype "input"))
      (node (ref "SR_D0") (pin "16") (pinfunction "VCC_16") (pintype "power_in"))
      (node (ref "SR_D1") (pin "10") (pinfunction "SCL_10") (pintype "input"))
      (node (ref "SR_D1") (pin "16") (pinfunction "VCC_16") (pintype "power_in"))
      (node (ref "SR_D2") (pin "10") (pinfunction "SCL_10") (pintype "input"))
      (node (ref "SR_D2") (pin "16") (pinfunction "VCC_16") (pintype "power_in"))
      (node (ref "U1") (pin "OUT") (pinfunction "OUT_OUT") (pintype "output"))
      (node (ref "U2") (pin "4") (pinfunction "VCC_4") (pintype "bidirectional"))
      (node (ref "U2") (pin "6") (pinfunction "VCC_6") (pintype "bidirectional"))
    )
    (net (code "97") (name "unconnected-(S1-O-Pad1)") (class "Default")
      (node (ref "S1") (pin "1") (pinfunction "O_1") (pintype "passive"))
    )
    (net (code "98") (name "unconnected-(S2-O-Pad1)") (class "Default")
      (node (ref "S2") (pin "1") (pinfunction "O_1") (pintype "passive"))
    )
    (net (code "99") (name "unconnected-(SR_D0-QH*-Pad9)") (class "Default")
      (node (ref "SR_D0") (pin "9") (pinfunction "QH*_9") (pintype "tri_state"))
    )
    (net (code "100") (name "unconnected-(SR_D0-QH-Pad7)") (class "Default")
      (node (ref "SR_D0") (pin "7") (pinfunction "QH_7") (pintype "tri_state"))
    )
    (net (code "101") (name "unconnected-(SR_D1-QH*-Pad9)") (class "Default")
      (node (ref "SR_D1") (pin "9") (pinfunction "QH*_9") (pintype "tri_state"))
    )
    (net (code "102") (name "unconnected-(SR_D1-QH-Pad7)") (class "Default")
      (node (ref "SR_D1") (pin "7") (pinfunction "QH_7") (pintype "tri_state"))
    )
    (net (code "103") (name "unconnected-(SR_D2-QH*-Pad9)") (class "Default")
      (node (ref "SR_D2") (pin "9") (pinfunction "QH*_9") (pintype "tri_state"))
    )
    (net (code "104") (name "unconnected-(SR_D2-QH-Pad7)") (class "Default")
      (node (ref "SR_D2") (pin "7") (pinfunction "QH_7") (pintype "tri_state"))
    )
    (net (code "105") (name "unconnected-(U2-ADC6-Pad19)") (class "Default")
      (node (ref "U2") (pin "19") (pinfunction "ADC6_19") (pintype "bidirectional"))
    )
    (net (code "106") (name "unconnected-(U2-ADC7-Pad22)") (class "Default")
      (node (ref "U2") (pin "22") (pinfunction "ADC7_22") (pintype "bidirectional"))
    )
    (net (code "107") (name "unconnected-(U2-AGND-Pad21)") (class "Default")
      (node (ref "U2") (pin "21") (pinfunction "AGND_21") (pintype "bidirectional"))
    )
    (net (code "108") (name "unconnected-(U2-AREF-Pad20)") (class "Default")
      (node (ref "U2") (pin "20") (pinfunction "AREF_20") (pintype "bidirectional"))
    )
    (net (code "109") (name "unconnected-(U2-AVCC-Pad18)") (class "Default")
      (node (ref "U2") (pin "18") (pinfunction "AVCC_18") (pintype "bidirectional"))
    )
    (net (code "110") (name "unconnected-(U2-PB6(XTAL1{slash}TOSC1)-Pad7)") (class "Default")
      (node (ref "U2") (pin "7") (pinfunction "PB6(XTAL1/TOSC1)_7") (pintype "bidirectional"))
    )
    (net (code "111") (name "unconnected-(U2-PB7(XTAL2{slash}TOSC2)-Pad8)") (class "Default")
      (node (ref "U2") (pin "8") (pinfunction "PB7(XTAL2/TOSC2)_8") (pintype "bidirectional"))
    )
  )
)
